# BV100011_ControlDEBUG.net
KiCad netlist of a schematic drawn in Altium Designer
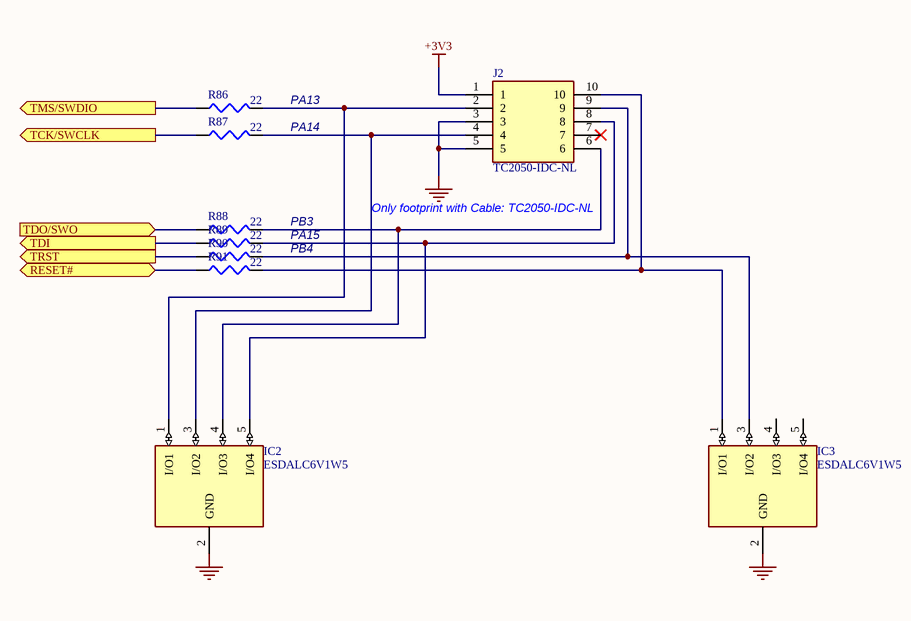
[diagram p0: BV100011_ControlDEBUG.SchDoc]

(export (version "E")
  (design (tool "Eeschema 10.0.6"))
  (components
    (comp (ref "IC2")
      (value "ESDALC6V1W5")
      (footprint "SamacSys:SOT65P210X110-5N")
      (description "Integrated Circuit")
      (fields
        (field (name "MOUSER PART NUMBER") "511-ESDALC6V1W5")
        (field (name "RS PART NUMBER") "0250044P")
      )
      (libsource (lib "SamacSys") (part "ESDALC6V1W5"))
    )
    (comp (ref "IC3")
      (value "ESDALC6V1W5")
      (footprint "SamacSys:SOT65P210X110-5N")
      (description "Integrated Circuit")
      (fields
        (field (name "MOUSER PART NUMBER") "511-ESDALC6V1W5")
        (field (name "RS PART NUMBER") "0250044P")
      )
      (libsource (lib "SamacSys") (part "ESDALC6V1W5"))
    )
    (comp (ref "J2")
      (value "TC2050-IDC-NL")
      (footprint "CON_TAG-C_TC2050-IDC-NL")
      (description "Plug-Of-Nailsâ„¢ Adapter Cable")
      (fields (field (name "MF") "Tag-Connect LLC"))
      (libsource (lib "TC2050-IDC-NL") (part "TC2050-IDC-NL"))
    )
    (comp (ref "R86")
      (value "22")
      (footprint "J1-0603")
      (description "Resistor")
      (fields (field (name "PUBLISHER") "Altium Limited"))
      (libsource (lib "Miscellaneous Devices") (part "Res3"))
    )
    (comp (ref "R87")
      (value "22")
      (footprint "J1-0603")
      (description "Resistor")
      (fields (field (name "PUBLISHER") "Altium Limited"))
      (libsource (lib "Miscellaneous Devices") (part "Res3"))
    )
    (comp (ref "R88")
      (value "22")
      (footprint "J1-0603")
      (description "Resistor")
      (fields (field (name "PUBLISHER") "Altium Limited"))
      (libsource (lib "Miscellaneous Devices") (part "Res3"))
    )
    (comp (ref "R89")
      (value "22")
      (footprint "J1-0603")
      (description "Resistor")
      (fields (field (name "PUBLISHER") "Altium Limited"))
      (libsource (lib "Miscellaneous Devices") (part "Res3"))
    )
    (comp (ref "R90")
      (value "22")
      (footprint "J1-0603")
      (description "Resistor")
      (fields (field (name "PUBLISHER") "Altium Limited"))
      (libsource (lib "Miscellaneous Devices") (part "Res3"))
    )
    (comp (ref "R91")
      (value "22")
      (footprint "J1-0603")
      (description "Resistor")
      (fields (field (name "PUBLISHER") "Altium Limited"))
      (libsource (lib "Miscellaneous Devices") (part "Res3"))
    )
  )
  (nets
    (net (code "1") (name "+3V3") (class "Default")
      (node (ref "J2") (pin "1") (pinfunction "1_1") (pintype "passive"))
    )
    (net (code "2") (name "/RESET#") (class "Default")
      (node (ref "R91") (pin "1") (pinfunction "1_1") (pintype "passive"))
    )
    (net (code "3") (name "/TCK{slash}SWCLK") (class "Default")
      (node (ref "R87") (pin "1") (pinfunction "1_1") (pintype "passive"))
    )
    (net (code "4") (name "/TDI") (class "Default")
      (node (ref "R89") (pin "1") (pinfunction "1_1") (pintype "passive"))
    )
    (net (code "5") (name "/TDO{slash}SWO") (class "Default")
      (node (ref "R88") (pin "1") (pinfunction "1_1") (pintype "passive"))
    )
    (net (code "6") (name "/TMS{slash}SWDIO") (class "Default")
      (node (ref "R86") (pin "1") (pinfunction "1_1") (pintype "passive"))
    )
    (net (code "7") (name "/TRST") (class "Default")
      (node (ref "R90") (pin "1") (pinfunction "1_1") (pintype "passive"))
    )
    (net (code "8") (name "GND") (class "Default")
      (node (ref "IC2") (pin "2") (pinfunction "GND_2") (pintype "power_in"))
      (node (ref "IC3") (pin "2") (pinfunction "GND_2") (pintype "power_in"))
      (node (ref "J2") (pin "3") (pinfunction "3_3") (pintype "passive"))
      (node (ref "J2") (pin "5") (pinfunction "5_5") (pintype "passive"))
    )
    (net (code "9") (name "Net-(IC2-I{slash}O1)") (class "Default")
      (node (ref "IC2") (pin "1") (pinfunction "I/O1_1") (pintype "bidirectional"))
      (node (ref "J2") (pin "2") (pinfunction "2_2") (pintype "passive"))
      (node (ref "R86") (pin "2") (pinfunction "2_2") (pintype "passive"))
    )
    (net (code "10") (name "Net-(IC2-I{slash}O2)") (class "Default")
      (node (ref "IC2") (pin "3") (pinfunction "I/O2_3") (pintype "bidirectional"))
      (node (ref "J2") (pin "4") (pinfunction "4_4") (pintype "passive"))
      (node (ref "R87") (pin "2") (pinfunction "2_2") (pintype "passive"))
    )
    (net (code "11") (name "Net-(IC2-I{slash}O3)") (class "Default")
      (node (ref "IC2") (pin "4") (pinfunction "I/O3_4") (pintype "bidirectional"))
      (node (ref "J2") (pin "6") (pinfunction "6_6") (pintype "passive"))
      (node (ref "R88") (pin "2") (pinfunction "2_2") (pintype "passive"))
    )
    (net (code "12") (name "Net-(IC2-I{slash}O4)") (class "Default")
      (node (ref "IC2") (pin "5") (pinfunction "I/O4_5") (pintype "bidirectional"))
      (node (ref "J2") (pin "8") (pinfunction "8_8") (pintype "passive"))
      (node (ref "R89") (pin "2") (pinfunction "2_2") (pintype "passive"))
    )
    (net (code "13") (name "Net-(IC3-I{slash}O1)") (class "Default")
      (node (ref "IC3") (pin "1") (pinfunction "I/O1_1") (pintype "bidirectional"))
      (node (ref "J2") (pin "10") (pinfunction "10_10") (pintype "passive"))
      (node (ref "R91") (pin "2") (pinfunction "2_2") (pintype "passive"))
    )
    (net (code "14") (name "Net-(IC3-I{slash}O2)") (class "Default")
      (node (ref "IC3") (pin "3") (pinfunction "I/O2_3") (pintype "bidirectional"))
      (node (ref "J2") (pin "9") (pinfunction "9_9") (pintype "passive"))
      (node (ref "R90") (pin "2") (pinfunction "2_2") (pintype "passive"))
    )
    (net (code "15") (name "unconnected-(IC3-I{slash}O3-Pad4)") (class "Default")
      (node (ref "IC3") (pin "4") (pinfunction "I/O3_4") (pintype "bidirectional"))
    )
    (net (code "16") (name "unconnected-(IC3-I{slash}O4-Pad5)") (class "Default")
      (node (ref "IC3") (pin "5") (pinfunction "I/O4_5") (pintype "bidirectional"))
    )
    (net (code "17") (name "unconnected-(J2-Pad7)") (class "Default")
      (node (ref "J2") (pin "7") (pinfunction "7_7") (pintype "passive+no_connect"))
    )
  )
)
